# RobotiCrawler.net
KiCad netlist of a schematic drawn in EasyEDA
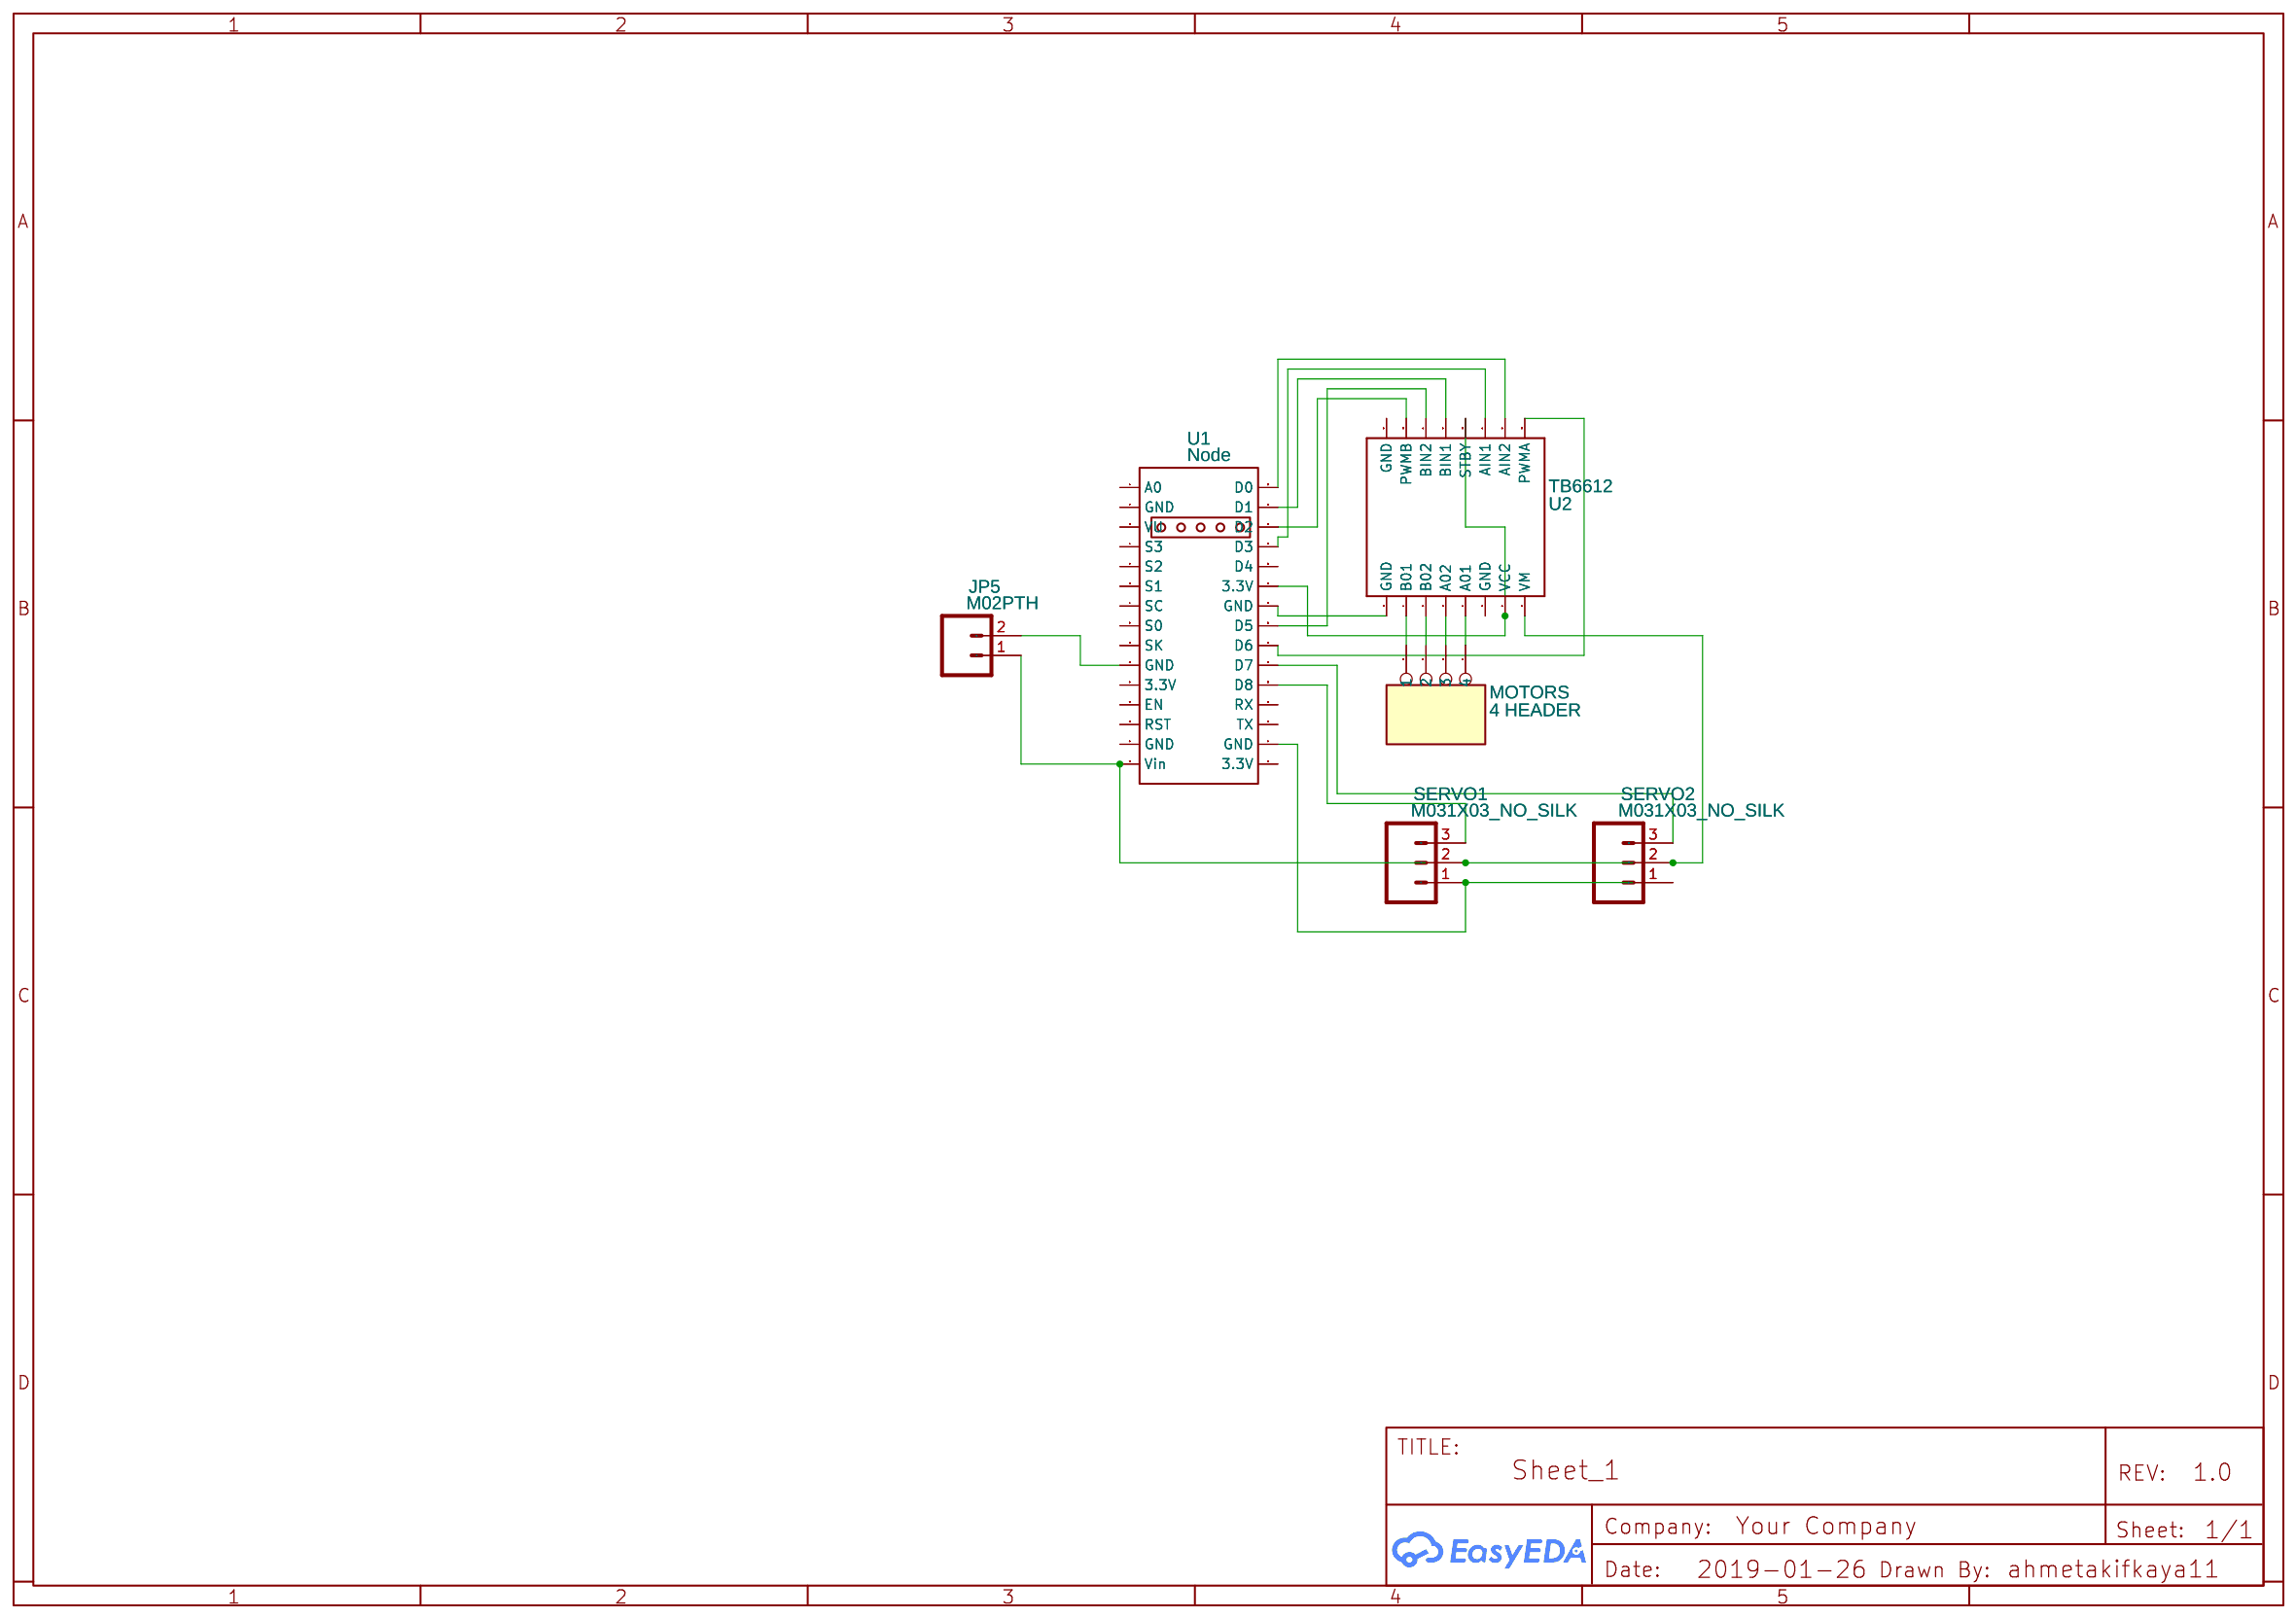
[diagram p0: schematic sheet]

(export (version "E")
  (design (tool "Eeschema 10.0.6"))
  (components
    (comp (ref "JP5")
      (value "M02PTH")
      (fields (field (name "BOM_Manufacturer Part") "?"))
      (libsource (lib "") (part "Unknown_480_325"))
    )
    (comp (ref "MOTORS")
      (value "4 HEADER")
      (fields (field (name "BOM_Manufacturer Part") "?"))
      (libsource (lib "") (part "Unknown_720_345"))
    )
    (comp (ref "SERVO1")
      (value "M031X03_NO_SILK")
      (fields (field (name "BOM_Manufacturer Part") "?"))
      (libsource (lib "") (part "Unknown_715_430"))
    )
    (comp (ref "SERVO2")
      (value "M031X03_NO_SILK")
      (fields (field (name "BOM_Manufacturer Part") "?"))
      (libsource (lib "") (part "Unknown_820_430"))
    )
    (comp (ref "U1")
      (value "Node")
      (fields (field (name "BOM_Manufacturer Part") "NodeMcu V3 LoLin"))
      (libsource (lib "") (part "Unknown_600_300"))
    )
    (comp (ref "U2")
      (value "TB6612")
      (fields (field (name "BOM_Manufacturer Part") "?"))
      (libsource (lib "") (part "Unknown_775_255"))
    )
  )
  (nets
    (net (code "1") (name "Net-(JP5-Pad2)") (class "Default")
      (node (ref "JP5") (pin "2") (pinfunction "2_2") (pintype "unspecified"))
      (node (ref "U1") (pin "10") (pinfunction "GND_10") (pintype "unspecified"))
    )
    (net (code "2") (name "Net-(SERVO1-Pad1)") (class "Default")
      (node (ref "SERVO1") (pin "1") (pinfunction "1_1") (pintype "unspecified"))
      (node (ref "SERVO2") (pin "1") (pinfunction "1_1") (pintype "unspecified"))
      (node (ref "U1") (pin "17") (pinfunction "GND_17") (pintype "unspecified"))
    )
    (net (code "3") (name "Net-(U1-D0)") (class "Default")
      (node (ref "U1") (pin "30") (pinfunction "D0_30") (pintype "unspecified"))
      (node (ref "U2") (pin "15") (pinfunction "AIN2_15") (pintype "unspecified"))
    )
    (net (code "4") (name "Net-(U1-D1)") (class "Default")
      (node (ref "U1") (pin "29") (pinfunction "D1_29") (pintype "unspecified"))
      (node (ref "U2") (pin "12") (pinfunction "BIN1_12") (pintype "unspecified"))
    )
    (net (code "5") (name "Net-(U1-D2)") (class "Default")
      (node (ref "U1") (pin "28") (pinfunction "D2_28") (pintype "unspecified"))
      (node (ref "U2") (pin "10") (pinfunction "PWMB_10") (pintype "unspecified"))
    )
    (net (code "6") (name "Net-(U1-D3)") (class "Default")
      (node (ref "U1") (pin "27") (pinfunction "D3_27") (pintype "unspecified"))
      (node (ref "U2") (pin "14") (pinfunction "AIN1_14") (pintype "unspecified"))
    )
    (net (code "7") (name "Net-(U1-D5)") (class "Default")
      (node (ref "U1") (pin "23") (pinfunction "D5_23") (pintype "unspecified"))
      (node (ref "U2") (pin "11") (pinfunction "BIN2_11") (pintype "unspecified"))
    )
    (net (code "8") (name "Net-(U1-D6)") (class "Default")
      (node (ref "U1") (pin "22") (pinfunction "D6_22") (pintype "unspecified"))
      (node (ref "U2") (pin "16") (pinfunction "PWMA_16") (pintype "unspecified"))
    )
    (net (code "9") (name "Net-(U1-D7)") (class "Default")
      (node (ref "SERVO2") (pin "3") (pinfunction "3_3") (pintype "unspecified"))
      (node (ref "U1") (pin "21") (pinfunction "D7_21") (pintype "unspecified"))
    )
    (net (code "10") (name "Net-(U1-D8)") (class "Default")
      (node (ref "SERVO1") (pin "3") (pinfunction "3_3") (pintype "unspecified"))
      (node (ref "U1") (pin "20") (pinfunction "D8_20") (pintype "unspecified"))
    )
    (net (code "11") (name "Net-(U1-GND-Pad24)") (class "Default")
      (node (ref "U1") (pin "24") (pinfunction "GND_24") (pintype "unspecified"))
      (node (ref "U2") (pin "8") (pinfunction "GND_8") (pintype "passive"))
    )
    (net (code "12") (name "Net-(U1-Vin)") (class "Default")
      (node (ref "JP5") (pin "1") (pinfunction "1_1") (pintype "unspecified"))
      (node (ref "SERVO1") (pin "2") (pinfunction "2_2") (pintype "unspecified"))
      (node (ref "SERVO2") (pin "2") (pinfunction "2_2") (pintype "unspecified"))
      (node (ref "U1") (pin "15") (pinfunction "Vin_15") (pintype "unspecified"))
      (node (ref "U2") (pin "1") (pinfunction "VM_1") (pintype "passive"))
    )
    (net (code "13") (name "Net-(U2-A01)") (class "Default")
      (node (ref "MOTORS") (pin "4") (pinfunction "4_4") (pintype "unspecified"))
      (node (ref "U2") (pin "4") (pinfunction "A01_4") (pintype "unspecified"))
    )
    (net (code "14") (name "Net-(U2-A02)") (class "Default")
      (node (ref "MOTORS") (pin "3") (pinfunction "3_3") (pintype "unspecified"))
      (node (ref "U2") (pin "5") (pinfunction "A02_5") (pintype "unspecified"))
    )
    (net (code "15") (name "Net-(U2-B01)") (class "Default")
      (node (ref "MOTORS") (pin "1") (pinfunction "1_1") (pintype "unspecified"))
      (node (ref "U2") (pin "7") (pinfunction "B01_7") (pintype "unspecified"))
    )
    (net (code "16") (name "Net-(U2-B02)") (class "Default")
      (node (ref "MOTORS") (pin "2") (pinfunction "2_2") (pintype "unspecified"))
      (node (ref "U2") (pin "6") (pinfunction "B02_6") (pintype "unspecified"))
    )
    (net (code "17") (name "Net-(U2-STBY)") (class "Default")
      (node (ref "U1") (pin "25") (pinfunction "3.3V_25") (pintype "unspecified"))
      (node (ref "U2") (pin "13") (pinfunction "STBY_13") (pintype "unspecified"))
      (node (ref "U2") (pin "2") (pinfunction "VCC_2") (pintype "passive"))
    )
    (net (code "18") (name "unconnected-(U1-3.3V-Pad11)") (class "Default")
      (node (ref "U1") (pin "11") (pinfunction "3.3V_11") (pintype "unspecified"))
    )
    (net (code "19") (name "unconnected-(U1-3.3V-Pad16)") (class "Default")
      (node (ref "U1") (pin "16") (pinfunction "3.3V_16") (pintype "unspecified"))
    )
    (net (code "20") (name "unconnected-(U1-A0-Pad1)") (class "Default")
      (node (ref "U1") (pin "1") (pinfunction "A0_1") (pintype "unspecified"))
    )
    (net (code "21") (name "unconnected-(U1-D4-Pad26)") (class "Default")
      (node (ref "U1") (pin "26") (pinfunction "D4_26") (pintype "unspecified"))
    )
    (net (code "22") (name "unconnected-(U1-EN-Pad12)") (class "Default")
      (node (ref "U1") (pin "12") (pinfunction "EN_12") (pintype "unspecified"))
    )
    (net (code "23") (name "unconnected-(U1-GND-Pad2)") (class "Default")
      (node (ref "U1") (pin "2") (pinfunction "GND_2") (pintype "unspecified"))
    )
    (net (code "24") (name "unconnected-(U1-GND-Pad14)") (class "Default")
      (node (ref "U1") (pin "14") (pinfunction "GND_14") (pintype "unspecified"))
    )
    (net (code "25") (name "unconnected-(U1-RST-Pad13)") (class "Default")
      (node (ref "U1") (pin "13") (pinfunction "RST_13") (pintype "unspecified"))
    )
    (net (code "26") (name "unconnected-(U1-RX-Pad19)") (class "Default")
      (node (ref "U1") (pin "19") (pinfunction "RX_19") (pintype "unspecified"))
    )
    (net (code "27") (name "unconnected-(U1-S0-Pad8)") (class "Default")
      (node (ref "U1") (pin "8") (pinfunction "S0_8") (pintype "unspecified"))
    )
    (net (code "28") (name "unconnected-(U1-S1-Pad6)") (class "Default")
      (node (ref "U1") (pin "6") (pinfunction "S1_6") (pintype "unspecified"))
    )
    (net (code "29") (name "unconnected-(U1-S2-Pad5)") (class "Default")
      (node (ref "U1") (pin "5") (pinfunction "S2_5") (pintype "unspecified"))
    )
    (net (code "30") (name "unconnected-(U1-S3-Pad4)") (class "Default")
      (node (ref "U1") (pin "4") (pinfunction "S3_4") (pintype "unspecified"))
    )
    (net (code "31") (name "unconnected-(U1-SC-Pad7)") (class "Default")
      (node (ref "U1") (pin "7") (pinfunction "SC_7") (pintype "unspecified"))
    )
    (net (code "32") (name "unconnected-(U1-SK-Pad9)") (class "Default")
      (node (ref "U1") (pin "9") (pinfunction "SK_9") (pintype "unspecified"))
    )
    (net (code "33") (name "unconnected-(U1-TX-Pad18)") (class "Default")
      (node (ref "U1") (pin "18") (pinfunction "TX_18") (pintype "unspecified"))
    )
    (net (code "34") (name "unconnected-(U1-VU-Pad3)") (class "Default")
      (node (ref "U1") (pin "3") (pinfunction "VU_3") (pintype "unspecified"))
    )
    (net (code "35") (name "unconnected-(U2-GND-Pad3)") (class "Default")
      (node (ref "U2") (pin "3") (pinfunction "GND_3") (pintype "passive"))
    )
    (net (code "36") (name "unconnected-(U2-GND-Pad9)") (class "Default")
      (node (ref "U2") (pin "9") (pinfunction "GND_9") (pintype "passive"))
    )
  )
)
